# InputCurrentSensingSketch.net
KiCad netlist of a schematic drawn in Altium Designer
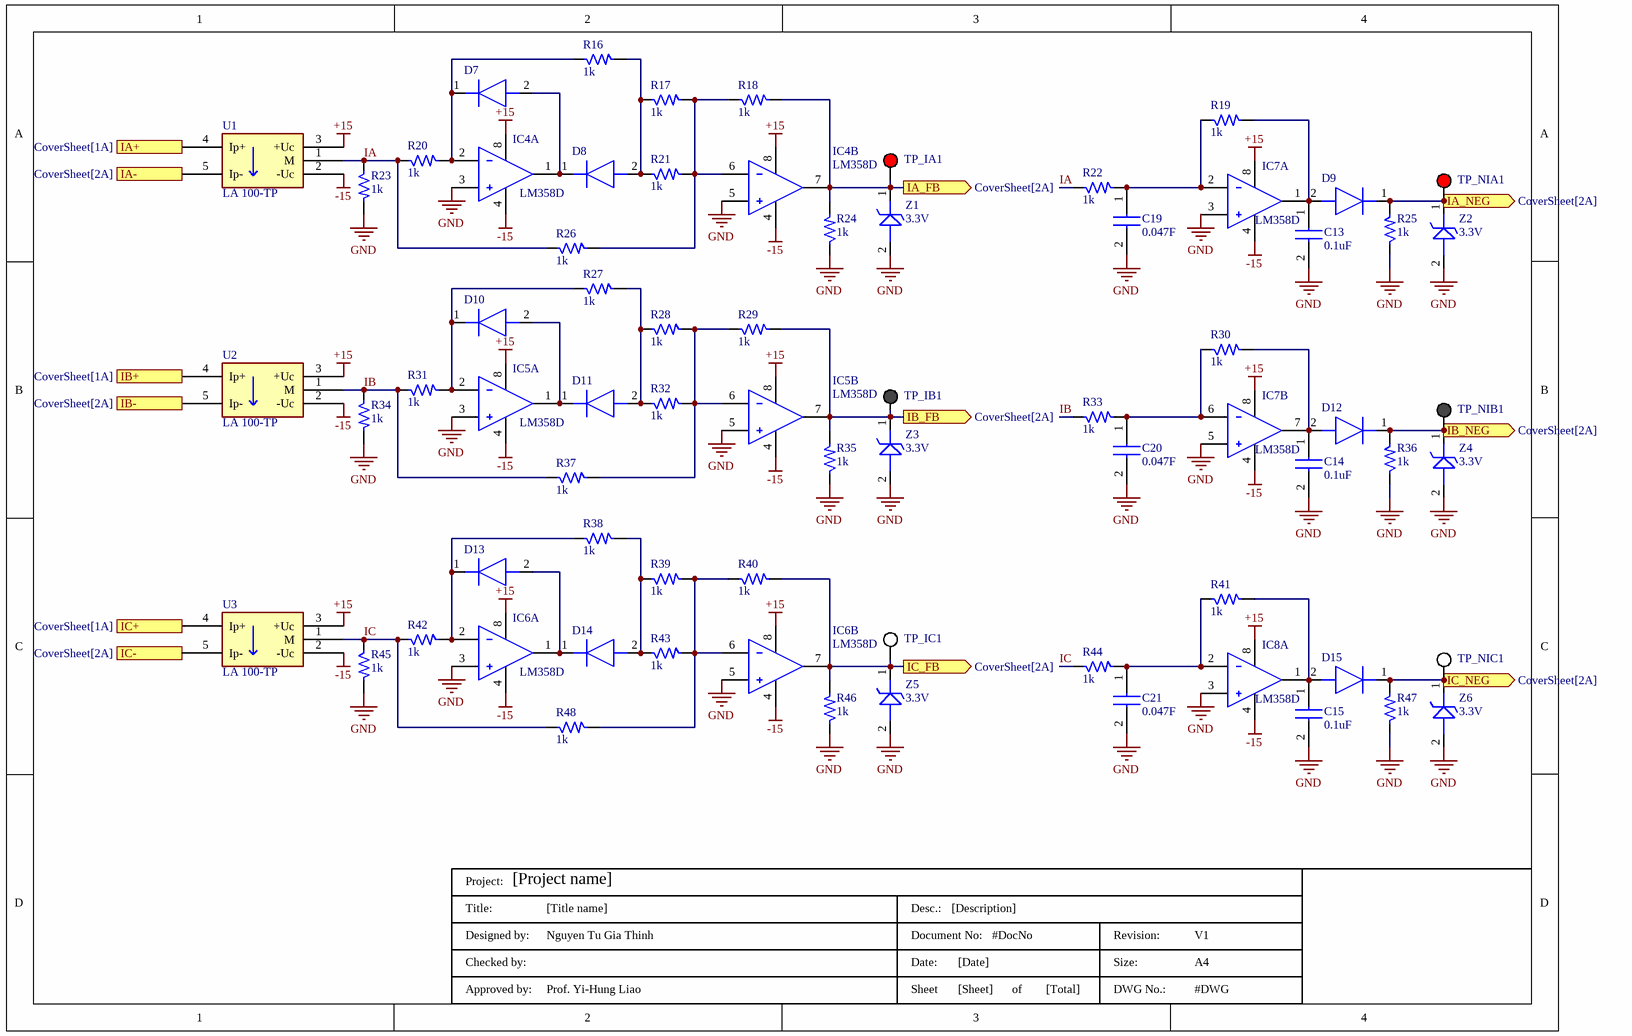
[diagram p0: InputCurrentSensingSketch.SchDoc]

(export (version "E")
  (design (tool "Eeschema 10.0.6"))
  (components
    (comp (ref "C13")
      (value "0.1uF")
      (footprint "SamacSys:C0805")
      (description "Capacitor")
      (fields
        (field (name "MANUFACTURER_PART_NUMBER") "C0805C104K3RACTU")
        (field (name "MOUSER PART NUMBER") "80-C0805C104K3R")
      )
      (libsource (lib "SamacSys") (part "C0805C104K3RACTU"))
    )
    (comp (ref "C14")
      (value "0.1uF")
      (footprint "SamacSys:C0805")
      (description "Capacitor")
      (fields
        (field (name "MANUFACTURER_PART_NUMBER") "C0805C104K3RACTU")
        (field (name "MOUSER PART NUMBER") "80-C0805C104K3R")
      )
      (libsource (lib "SamacSys") (part "C0805C104K3RACTU"))
    )
    (comp (ref "C15")
      (value "0.1uF")
      (footprint "SamacSys:C0805")
      (description "Capacitor")
      (fields
        (field (name "MANUFACTURER_PART_NUMBER") "C0805C104K3RACTU")
        (field (name "MOUSER PART NUMBER") "80-C0805C104K3R")
      )
      (libsource (lib "SamacSys") (part "C0805C104K3RACTU"))
    )
    (comp (ref "C19")
      (value "0.047F")
      (footprint "SamacSys:C0805")
      (description "Capacitor")
      (fields
        (field (name "MANUFACTURER_PART_NUMBER") "C0805C473F3GECAUTO7210")
        (field (name "MOUSER PART NUMBER") "80-C0805C473F3GEAULR")
      )
      (libsource (lib "*") (part "C0805C473F3GECAUTO7210"))
    )
    (comp (ref "C20")
      (value "0.047F")
      (footprint "SamacSys:C0805")
      (description "Capacitor")
      (fields
        (field (name "MANUFACTURER_PART_NUMBER") "C0805C473F3GECAUTO7210")
        (field (name "MOUSER PART NUMBER") "80-C0805C473F3GEAULR")
      )
      (libsource (lib "*") (part "C0805C473F3GECAUTO7210"))
    )
    (comp (ref "C21")
      (value "0.047F")
      (footprint "SamacSys:C0805")
      (description "Capacitor")
      (fields
        (field (name "MANUFACTURER_PART_NUMBER") "C0805C473F3GECAUTO7210")
        (field (name "MOUSER PART NUMBER") "80-C0805C473F3GEAULR")
      )
      (libsource (lib "*") (part "C0805C473F3GECAUTO7210"))
    )
    (comp (ref "D7")
      (value "MBRM130LT1G")
      (footprint "SamacSys:MBRM130LT1G")
      (description "Diode")
      (fields (field (name "MOUSER PART NUMBER") "863-MBRM130LT1G"))
      (libsource (lib "SamacSys") (part "MBRM130LT1G"))
    )
    (comp (ref "D8")
      (value "MBRM130LT1G")
      (footprint "SamacSys:MBRM130LT1G")
      (description "Diode")
      (fields (field (name "MOUSER PART NUMBER") "863-MBRM130LT1G"))
      (libsource (lib "SamacSys") (part "MBRM130LT1G"))
    )
    (comp (ref "D9")
      (value "MBRM130LT1G")
      (footprint "SamacSys:MBRM130LT1G")
      (description "Diode")
      (fields (field (name "MOUSER PART NUMBER") "863-MBRM130LT1G"))
      (libsource (lib "SamacSys") (part "MBRM130LT1G"))
    )
    (comp (ref "D10")
      (value "MBRM130LT1G")
      (footprint "SamacSys:MBRM130LT1G")
      (description "Diode")
      (fields (field (name "MOUSER PART NUMBER") "863-MBRM130LT1G"))
      (libsource (lib "SamacSys") (part "MBRM130LT1G"))
    )
    (comp (ref "D11")
      (value "MBRM130LT1G")
      (footprint "SamacSys:MBRM130LT1G")
      (description "Diode")
      (fields (field (name "MOUSER PART NUMBER") "863-MBRM130LT1G"))
      (libsource (lib "SamacSys") (part "MBRM130LT1G"))
    )
    (comp (ref "D12")
      (value "MBRM130LT1G")
      (footprint "SamacSys:MBRM130LT1G")
      (description "Diode")
      (fields (field (name "MOUSER PART NUMBER") "863-MBRM130LT1G"))
      (libsource (lib "SamacSys") (part "MBRM130LT1G"))
    )
    (comp (ref "D13")
      (value "MBRM130LT1G")
      (footprint "SamacSys:MBRM130LT1G")
      (description "Diode")
      (fields (field (name "MOUSER PART NUMBER") "863-MBRM130LT1G"))
      (libsource (lib "SamacSys") (part "MBRM130LT1G"))
    )
    (comp (ref "D14")
      (value "MBRM130LT1G")
      (footprint "SamacSys:MBRM130LT1G")
      (description "Diode")
      (fields (field (name "MOUSER PART NUMBER") "863-MBRM130LT1G"))
      (libsource (lib "SamacSys") (part "MBRM130LT1G"))
    )
    (comp (ref "D15")
      (value "MBRM130LT1G")
      (footprint "SamacSys:MBRM130LT1G")
      (description "Diode")
      (fields (field (name "MOUSER PART NUMBER") "863-MBRM130LT1G"))
      (libsource (lib "SamacSys") (part "MBRM130LT1G"))
    )
    (comp (ref "IC4")
      (value "LM358D")
      (footprint "SamacSys:SOIC127P600X175-8N")
      (description "Integrated Circuit")
      (fields (field (name "MOUSER PART NUMBER") "595-LM358D"))
      (libsource (lib "ViennaRectifier") (part "LM358D"))
    )
    (comp (ref "IC5")
      (value "LM358D")
      (footprint "SamacSys:SOIC127P600X175-8N")
      (description "Integrated Circuit")
      (fields (field (name "MOUSER PART NUMBER") "595-LM358D"))
      (libsource (lib "ViennaRectifier") (part "LM358D"))
    )
    (comp (ref "IC6")
      (value "LM358D")
      (footprint "SamacSys:SOIC127P600X175-8N")
      (description "Integrated Circuit")
      (fields (field (name "MOUSER PART NUMBER") "595-LM358D"))
      (libsource (lib "ViennaRectifier") (part "LM358D"))
    )
    (comp (ref "IC7")
      (value "LM358D")
      (footprint "SamacSys:SOIC127P600X175-8N")
      (description "Integrated Circuit")
      (fields (field (name "MOUSER PART NUMBER") "595-LM358D"))
      (libsource (lib "ViennaRectifier") (part "LM358D"))
    )
    (comp (ref "IC8")
      (value "LM358D")
      (footprint "SamacSys:SOIC127P600X175-8N")
      (description "Integrated Circuit")
      (fields (field (name "MOUSER PART NUMBER") "595-LM358D"))
      (libsource (lib "ViennaRectifier") (part "LM358D"))
    )
    (comp (ref "R16")
      (value "1k")
      (footprint "SM-1206")
      (description "Resistor 1/4W")
      (libsource (lib "ViennaRectifier") (part "R"))
    )
    (comp (ref "R17")
      (value "1k")
      (footprint "SM-1206")
      (description "Resistor 1/4W")
      (libsource (lib "ViennaRectifier") (part "R"))
    )
    (comp (ref "R18")
      (value "1k")
      (footprint "SM-1206")
      (description "Resistor 1/4W")
      (libsource (lib "ViennaRectifier") (part "R"))
    )
    (comp (ref "R19")
      (value "1k")
      (footprint "SM-1206")
      (description "Resistor 1/4W")
      (libsource (lib "ViennaRectifier") (part "R"))
    )
    (comp (ref "R20")
      (value "1k")
      (footprint "SM-1206")
      (description "Resistor 1/4W")
      (libsource (lib "ViennaRectifier") (part "R"))
    )
    (comp (ref "R21")
      (value "1k")
      (footprint "SM-1206")
      (description "Resistor 1/4W")
      (libsource (lib "ViennaRectifier") (part "R"))
    )
    (comp (ref "R22")
      (value "1k")
      (footprint "SM-1206")
      (description "Resistor 1/4W")
      (libsource (lib "ViennaRectifier") (part "R"))
    )
    (comp (ref "R23")
      (value "1k")
      (footprint "SM-1206")
      (description "Resistor 1/4W")
      (libsource (lib "ViennaRectifier") (part "R"))
    )
    (comp (ref "R24")
      (value "1k")
      (footprint "SM-1206")
      (description "Resistor 1/4W")
      (libsource (lib "ViennaRectifier") (part "R"))
    )
    (comp (ref "R25")
      (value "1k")
      (footprint "SM-1206")
      (description "Resistor 1/4W")
      (libsource (lib "ViennaRectifier") (part "R"))
    )
    (comp (ref "R26")
      (value "1k")
      (footprint "SM-1206")
      (description "Resistor 1/4W")
      (libsource (lib "ViennaRectifier") (part "R"))
    )
    (comp (ref "R27")
      (value "1k")
      (footprint "SM-1206")
      (description "Resistor 1/4W")
      (libsource (lib "ViennaRectifier") (part "R"))
    )
    (comp (ref "R28")
      (value "1k")
      (footprint "SM-1206")
      (description "Resistor 1/4W")
      (libsource (lib "ViennaRectifier") (part "R"))
    )
    (comp (ref "R29")
      (value "1k")
      (footprint "SM-1206")
      (description "Resistor 1/4W")
      (libsource (lib "ViennaRectifier") (part "R"))
    )
    (comp (ref "R30")
      (value "1k")
      (footprint "SM-1206")
      (description "Resistor 1/4W")
      (libsource (lib "ViennaRectifier") (part "R"))
    )
    (comp (ref "R31")
      (value "1k")
      (footprint "SM-1206")
      (description "Resistor 1/4W")
      (libsource (lib "ViennaRectifier") (part "R"))
    )
    (comp (ref "R32")
      (value "1k")
      (footprint "SM-1206")
      (description "Resistor 1/4W")
      (libsource (lib "ViennaRectifier") (part "R"))
    )
    (comp (ref "R33")
      (value "1k")
      (footprint "SM-1206")
      (description "Resistor 1/4W")
      (libsource (lib "ViennaRectifier") (part "R"))
    )
    (comp (ref "R34")
      (value "1k")
      (footprint "SM-1206")
      (description "Resistor 1/4W")
      (libsource (lib "ViennaRectifier") (part "R"))
    )
    (comp (ref "R35")
      (value "1k")
      (footprint "SM-1206")
      (description "Resistor 1/4W")
      (libsource (lib "ViennaRectifier") (part "R"))
    )
    (comp (ref "R36")
      (value "1k")
      (footprint "SM-1206")
      (description "Resistor 1/4W")
      (libsource (lib "ViennaRectifier") (part "R"))
    )
    (comp (ref "R37")
      (value "1k")
      (footprint "SM-1206")
      (description "Resistor 1/4W")
      (libsource (lib "ViennaRectifier") (part "R"))
    )
    (comp (ref "R38")
      (value "1k")
      (footprint "SM-1206")
      (description "Resistor 1/4W")
      (libsource (lib "ViennaRectifier") (part "R"))
    )
    (comp (ref "R39")
      (value "1k")
      (footprint "SM-1206")
      (description "Resistor 1/4W")
      (libsource (lib "ViennaRectifier") (part "R"))
    )
    (comp (ref "R40")
      (value "1k")
      (footprint "SM-1206")
      (description "Resistor 1/4W")
      (libsource (lib "ViennaRectifier") (part "R"))
    )
    (comp (ref "R41")
      (value "1k")
      (footprint "SM-1206")
      (description "Resistor 1/4W")
      (libsource (lib "ViennaRectifier") (part "R"))
    )
    (comp (ref "R42")
      (value "1k")
      (footprint "SM-1206")
      (description "Resistor 1/4W")
      (libsource (lib "ViennaRectifier") (part "R"))
    )
    (comp (ref "R43")
      (value "1k")
      (footprint "SM-1206")
      (description "Resistor 1/4W")
      (libsource (lib "ViennaRectifier") (part "R"))
    )
    (comp (ref "R44")
      (value "1k")
      (footprint "SM-1206")
      (description "Resistor 1/4W")
      (libsource (lib "ViennaRectifier") (part "R"))
    )
    (comp (ref "R45")
      (value "1k")
      (footprint "SM-1206")
      (description "Resistor 1/4W")
      (libsource (lib "ViennaRectifier") (part "R"))
    )
    (comp (ref "R46")
      (value "1k")
      (footprint "SM-1206")
      (description "Resistor 1/4W")
      (libsource (lib "ViennaRectifier") (part "R"))
    )
    (comp (ref "R47")
      (value "1k")
      (footprint "SM-1206")
      (description "Resistor 1/4W")
      (libsource (lib "ViennaRectifier") (part "R"))
    )
    (comp (ref "R48")
      (value "1k")
      (footprint "SM-1206")
      (description "Resistor 1/4W")
      (libsource (lib "ViennaRectifier") (part "R"))
    )
    (comp (ref "TP_IA1")
      (value "~")
      (footprint "5000")
      (description "Test Point Red, Multipurpose, TH")
      (libsource (lib "TestPointKeystone") (part "5000"))
    )
    (comp (ref "TP_IB1")
      (value "~")
      (footprint "5001")
      (description "Test Point Black, Multipurpose, TH")
      (libsource (lib "TestPointKeystone") (part "5001"))
    )
    (comp (ref "TP_IC1")
      (value "~")
      (footprint "5002")
      (description "Test Point White, Multipurpose, TH")
      (libsource (lib "TestPointKeystone") (part "5002"))
    )
    (comp (ref "TP_NIA1")
      (value "~")
      (footprint "5000")
      (description "Test Point Red, Multipurpose, TH")
      (libsource (lib "TestPointKeystone") (part "5000"))
    )
    (comp (ref "TP_NIB1")
      (value "~")
      (footprint "5001")
      (description "Test Point Black, Multipurpose, TH")
      (libsource (lib "TestPointKeystone") (part "5001"))
    )
    (comp (ref "TP_NIC1")
      (value "~")
      (footprint "5002")
      (description "Test Point White, Multipurpose, TH")
      (libsource (lib "TestPointKeystone") (part "5002"))
    )
    (comp (ref "U1")
      (value "LA 100-TP")
      (footprint "LA 100-TP")
      (description "Current Transducer, AC/AC, 100A")
      (libsource (lib "ViennaRectifier") (part "LA 100-TP"))
    )
    (comp (ref "U2")
      (value "LA 100-TP")
      (footprint "LA 100-TP")
      (description "Current Transducer, AC/AC, 100A")
      (libsource (lib "ViennaRectifier") (part "LA 100-TP"))
    )
    (comp (ref "U3")
      (value "LA 100-TP")
      (footprint "LA 100-TP")
      (description "Current Transducer, AC/AC, 100A")
      (libsource (lib "ViennaRectifier") (part "LA 100-TP"))
    )
    (comp (ref "Z1")
      (value "3.3V")
      (footprint "SamacSys:DIOM5226X230N")
      (description "Zener Diode")
      (fields
        (field (name "MANUFACTURER_PART_NUMBER") "BZG05C3V3-HM3-08")
        (field (name "MOUSER PART NUMBER") "78-BZG05C3V3-HM3-08")
      )
      (libsource (lib "SamacSys") (part "BZG05C3V3-HM3-08"))
    )
    (comp (ref "Z2")
      (value "3.3V")
      (footprint "SamacSys:DIOM5226X230N")
      (description "Zener Diode")
      (fields
        (field (name "MANUFACTURER_PART_NUMBER") "BZG05C3V3-HM3-08")
        (field (name "MOUSER PART NUMBER") "78-BZG05C3V3-HM3-08")
      )
      (libsource (lib "SamacSys") (part "BZG05C3V3-HM3-08"))
    )
    (comp (ref "Z3")
      (value "3.3V")
      (footprint "SamacSys:DIOM5226X230N")
      (description "Zener Diode")
      (fields
        (field (name "MANUFACTURER_PART_NUMBER") "BZG05C3V3-HM3-08")
        (field (name "MOUSER PART NUMBER") "78-BZG05C3V3-HM3-08")
      )
      (libsource (lib "SamacSys") (part "BZG05C3V3-HM3-08"))
    )
    (comp (ref "Z4")
      (value "3.3V")
      (footprint "SamacSys:DIOM5226X230N")
      (description "Zener Diode")
      (fields
        (field (name "MANUFACTURER_PART_NUMBER") "BZG05C3V3-HM3-08")
        (field (name "MOUSER PART NUMBER") "78-BZG05C3V3-HM3-08")
      )
      (libsource (lib "SamacSys") (part "BZG05C3V3-HM3-08"))
    )
    (comp (ref "Z5")
      (value "3.3V")
      (footprint "SamacSys:DIOM5226X230N")
      (description "Zener Diode")
      (fields
        (field (name "MANUFACTURER_PART_NUMBER") "BZG05C3V3-HM3-08")
        (field (name "MOUSER PART NUMBER") "78-BZG05C3V3-HM3-08")
      )
      (libsource (lib "SamacSys") (part "BZG05C3V3-HM3-08"))
    )
    (comp (ref "Z6")
      (value "3.3V")
      (footprint "SamacSys:DIOM5226X230N")
      (description "Zener Diode")
      (fields
        (field (name "MANUFACTURER_PART_NUMBER") "BZG05C3V3-HM3-08")
        (field (name "MOUSER PART NUMBER") "78-BZG05C3V3-HM3-08")
      )
      (libsource (lib "SamacSys") (part "BZG05C3V3-HM3-08"))
    )
  )
  (nets
    (net (code "1") (name "+15") (class "Default")
      (node (ref "IC4") (pin "8") (pinfunction "V+_8") (pintype "passive"))
      (node (ref "IC5") (pin "8") (pinfunction "V+_8") (pintype "passive"))
      (node (ref "IC6") (pin "8") (pinfunction "V+_8") (pintype "passive"))
      (node (ref "IC7") (pin "8") (pinfunction "V+_8") (pintype "passive"))
      (node (ref "IC8") (pin "8") (pinfunction "V+_8") (pintype "passive"))
      (node (ref "U1") (pin "3") (pinfunction "+Uc_3") (pintype "passive"))
      (node (ref "U2") (pin "3") (pinfunction "+Uc_3") (pintype "passive"))
      (node (ref "U3") (pin "3") (pinfunction "+Uc_3") (pintype "passive"))
    )
    (net (code "2") (name "-15") (class "Default")
      (node (ref "IC4") (pin "4") (pinfunction "V-_4") (pintype "passive"))
      (node (ref "IC5") (pin "4") (pinfunction "V-_4") (pintype "passive"))
      (node (ref "IC6") (pin "4") (pinfunction "V-_4") (pintype "passive"))
      (node (ref "IC7") (pin "4") (pinfunction "V-_4") (pintype "passive"))
      (node (ref "IC8") (pin "4") (pinfunction "V-_4") (pintype "passive"))
      (node (ref "U1") (pin "2") (pinfunction "-Uc_2") (pintype "passive"))
      (node (ref "U2") (pin "2") (pinfunction "-Uc_2") (pintype "passive"))
      (node (ref "U3") (pin "2") (pinfunction "-Uc_2") (pintype "passive"))
    )
    (net (code "3") (name "/IA") (class "Default")
      (node (ref "R20") (pin "1") (pinfunction "1_1") (pintype "passive"))
      (node (ref "R22") (pin "1") (pinfunction "1_1") (pintype "passive"))
      (node (ref "R23") (pin "1") (pinfunction "1_1") (pintype "passive"))
      (node (ref "R26") (pin "1") (pinfunction "1_1") (pintype "passive"))
      (node (ref "U1") (pin "1") (pinfunction "M_1") (pintype "passive"))
    )
    (net (code "4") (name "/IA+") (class "Default")
      (node (ref "U1") (pin "4") (pinfunction "Ip+_4") (pintype "passive"))
    )
    (net (code "5") (name "/IA-") (class "Default")
      (node (ref "U1") (pin "5") (pinfunction "Ip-_5") (pintype "passive"))
    )
    (net (code "6") (name "/IA_FB") (class "Default")
      (node (ref "IC4") (pin "7") (pinfunction "OUT2_7") (pintype "passive"))
      (node (ref "R18") (pin "2") (pinfunction "2_2") (pintype "passive"))
      (node (ref "R24") (pin "2") (pinfunction "2_2") (pintype "passive"))
      (node (ref "TP_IA1") (pin "1") (pinfunction "1_1") (pintype "passive"))
      (node (ref "Z1") (pin "1") (pinfunction "K_1") (pintype "passive"))
    )
    (net (code "7") (name "/IA_NEG") (class "Default")
      (node (ref "D9") (pin "1") (pinfunction "K_1") (pintype "passive"))
      (node (ref "R25") (pin "2") (pinfunction "2_2") (pintype "passive"))
      (node (ref "TP_NIA1") (pin "1") (pinfunction "1_1") (pintype "passive"))
      (node (ref "Z2") (pin "1") (pinfunction "K_1") (pintype "passive"))
    )
    (net (code "8") (name "/IB") (class "Default")
      (node (ref "R31") (pin "1") (pinfunction "1_1") (pintype "passive"))
      (node (ref "R33") (pin "1") (pinfunction "1_1") (pintype "passive"))
      (node (ref "R34") (pin "1") (pinfunction "1_1") (pintype "passive"))
      (node (ref "R37") (pin "1") (pinfunction "1_1") (pintype "passive"))
      (node (ref "U2") (pin "1") (pinfunction "M_1") (pintype "passive"))
    )
    (net (code "9") (name "/IB+") (class "Default")
      (node (ref "U2") (pin "4") (pinfunction "Ip+_4") (pintype "passive"))
    )
    (net (code "10") (name "/IB-") (class "Default")
      (node (ref "U2") (pin "5") (pinfunction "Ip-_5") (pintype "passive"))
    )
    (net (code "11") (name "/IB_FB") (class "Default")
      (node (ref "IC5") (pin "7") (pinfunction "OUT2_7") (pintype "passive"))
      (node (ref "R29") (pin "2") (pinfunction "2_2") (pintype "passive"))
      (node (ref "R35") (pin "2") (pinfunction "2_2") (pintype "passive"))
      (node (ref "TP_IB1") (pin "1") (pinfunction "1_1") (pintype "passive"))
      (node (ref "Z3") (pin "1") (pinfunction "K_1") (pintype "passive"))
    )
    (net (code "12") (name "/IB_NEG") (class "Default")
      (node (ref "D12") (pin "1") (pinfunction "K_1") (pintype "passive"))
      (node (ref "R36") (pin "2") (pinfunction "2_2") (pintype "passive"))
      (node (ref "TP_NIB1") (pin "1") (pinfunction "1_1") (pintype "passive"))
      (node (ref "Z4") (pin "1") (pinfunction "K_1") (pintype "passive"))
    )
    (net (code "13") (name "/IC") (class "Default")
      (node (ref "R42") (pin "1") (pinfunction "1_1") (pintype "passive"))
      (node (ref "R44") (pin "1") (pinfunction "1_1") (pintype "passive"))
      (node (ref "R45") (pin "1") (pinfunction "1_1") (pintype "passive"))
      (node (ref "R48") (pin "1") (pinfunction "1_1") (pintype "passive"))
      (node (ref "U3") (pin "1") (pinfunction "M_1") (pintype "passive"))
    )
    (net (code "14") (name "/IC+") (class "Default")
      (node (ref "U3") (pin "4") (pinfunction "Ip+_4") (pintype "passive"))
    )
    (net (code "15") (name "/IC-") (class "Default")
      (node (ref "U3") (pin "5") (pinfunction "Ip-_5") (pintype "passive"))
    )
    (net (code "16") (name "/IC_FB") (class "Default")
      (node (ref "IC6") (pin "7") (pinfunction "OUT2_7") (pintype "passive"))
      (node (ref "R40") (pin "2") (pinfunction "2_2") (pintype "passive"))
      (node (ref "R46") (pin "2") (pinfunction "2_2") (pintype "passive"))
      (node (ref "TP_IC1") (pin "1") (pinfunction "1_1") (pintype "passive"))
      (node (ref "Z5") (pin "1") (pinfunction "K_1") (pintype "passive"))
    )
    (net (code "17") (name "/IC_NEG") (class "Default")
      (node (ref "D15") (pin "1") (pinfunction "K_1") (pintype "passive"))
      (node (ref "R47") (pin "2") (pinfunction "2_2") (pintype "passive"))
      (node (ref "TP_NIC1") (pin "1") (pinfunction "1_1") (pintype "passive"))
      (node (ref "Z6") (pin "1") (pinfunction "K_1") (pintype "passive"))
    )
    (net (code "18") (name "GND") (class "Default")
      (node (ref "C13") (pin "2") (pinfunction "2_2") (pintype "passive"))
      (node (ref "C14") (pin "2") (pinfunction "2_2") (pintype "passive"))
      (node (ref "C15") (pin "2") (pinfunction "2_2") (pintype "passive"))
      (node (ref "C19") (pin "2") (pinfunction "2_2") (pintype "passive"))
      (node (ref "C20") (pin "2") (pinfunction "2_2") (pintype "passive"))
      (node (ref "C21") (pin "2") (pinfunction "2_2") (pintype "passive"))
      (node (ref "IC4") (pin "3") (pinfunction "IN1+_3") (pintype "passive"))
      (node (ref "IC4") (pin "5") (pinfunction "IN2+_5") (pintype "passive"))
      (node (ref "IC5") (pin "3") (pinfunction "IN1+_3") (pintype "passive"))
      (node (ref "IC5") (pin "5") (pinfunction "IN2+_5") (pintype "passive"))
      (node (ref "IC6") (pin "3") (pinfunction "IN1+_3") (pintype "passive"))
      (node (ref "IC6") (pin "5") (pinfunction "IN2+_5") (pintype "passive"))
      (node (ref "IC7") (pin "3") (pinfunction "IN1+_3") (pintype "passive"))
      (node (ref "IC7") (pin "5") (pinfunction "IN2+_5") (pintype "passive"))
      (node (ref "IC8") (pin "3") (pinfunction "IN1+_3") (pintype "passive"))
      (node (ref "R23") (pin "2") (pinfunction "2_2") (pintype "passive"))
      (node (ref "R24") (pin "1") (pinfunction "1_1") (pintype "passive"))
      (node (ref "R25") (pin "1") (pinfunction "1_1") (pintype "passive"))
      (node (ref "R34") (pin "2") (pinfunction "2_2") (pintype "passive"))
      (node (ref "R35") (pin "1") (pinfunction "1_1") (pintype "passive"))
      (node (ref "R36") (pin "1") (pinfunction "1_1") (pintype "passive"))
      (node (ref "R45") (pin "2") (pinfunction "2_2") (pintype "passive"))
      (node (ref "R46") (pin "1") (pinfunction "1_1") (pintype "passive"))
      (node (ref "R47") (pin "1") (pinfunction "1_1") (pintype "passive"))
      (node (ref "Z1") (pin "2") (pinfunction "A_2") (pintype "passive"))
      (node (ref "Z2") (pin "2") (pinfunction "A_2") (pintype "passive"))
      (node (ref "Z3") (pin "2") (pinfunction "A_2") (pintype "passive"))
      (node (ref "Z4") (pin "2") (pinfunction "A_2") (pintype "passive"))
      (node (ref "Z5") (pin "2") (pinfunction "A_2") (pintype "passive"))
      (node (ref "Z6") (pin "2") (pinfunction "A_2") (pintype "passive"))
    )
    (net (code "19") (name "Net-(D7-A)") (class "Default")
      (node (ref "D7") (pin "2") (pinfunction "A_2") (pintype "passive"))
      (node (ref "D8") (pin "1") (pinfunction "K_1") (pintype "passive"))
      (node (ref "IC4") (pin "1") (pinfunction "OUT1_1") (pintype "passive"))
    )
    (net (code "20") (name "Net-(D7-K)") (class "Default")
      (node (ref "D7") (pin "1") (pinfunction "K_1") (pintype "passive"))
      (node (ref "IC4") (pin "2") (pinfunction "IN1-_2") (pintype "passive"))
      (node (ref "R16") (pin "1") (pinfunction "1_1") (pintype "passive"))
      (node (ref "R20") (pin "2") (pinfunction "2_2") (pintype "passive"))
    )
    (net (code "21") (name "Net-(D8-A)") (class "Default")
      (node (ref "D8") (pin "2") (pinfunction "A_2") (pintype "passive"))
      (node (ref "R16") (pin "2") (pinfunction "2_2") (pintype "passive"))
      (node (ref "R17") (pin "1") (pinfunction "1_1") (pintype "passive"))
      (node (ref "R21") (pin "1") (pinfunction "1_1") (pintype "passive"))
    )
    (net (code "22") (name "Net-(D9-A)") (class "Default")
      (node (ref "C13") (pin "1") (pinfunction "1_1") (pintype "passive"))
      (node (ref "D9") (pin "2") (pinfunction "A_2") (pintype "passive"))
      (node (ref "IC7") (pin "1") (pinfunction "OUT1_1") (pintype "passive"))
      (node (ref "R19") (pin "2") (pinfunction "2_2") (pintype "passive"))
    )
    (net (code "23") (name "Net-(D10-A)") (class "Default")
      (node (ref "D10") (pin "2") (pinfunction "A_2") (pintype "passive"))
      (node (ref "D11") (pin "1") (pinfunction "K_1") (pintype "passive"))
      (node (ref "IC5") (pin "1") (pinfunction "OUT1_1") (pintype "passive"))
    )
    (net (code "24") (name "Net-(D10-K)") (class "Default")
      (node (ref "D10") (pin "1") (pinfunction "K_1") (pintype "passive"))
      (node (ref "IC5") (pin "2") (pinfunction "IN1-_2") (pintype "passive"))
      (node (ref "R27") (pin "1") (pinfunction "1_1") (pintype "passive"))
      (node (ref "R31") (pin "2") (pinfunction "2_2") (pintype "passive"))
    )
    (net (code "25") (name "Net-(D11-A)") (class "Default")
      (node (ref "D11") (pin "2") (pinfunction "A_2") (pintype "passive"))
      (node (ref "R27") (pin "2") (pinfunction "2_2") (pintype "passive"))
      (node (ref "R28") (pin "1") (pinfunction "1_1") (pintype "passive"))
      (node (ref "R32") (pin "1") (pinfunction "1_1") (pintype "passive"))
    )
    (net (code "26") (name "Net-(D12-A)") (class "Default")
      (node (ref "C14") (pin "1") (pinfunction "1_1") (pintype "passive"))
      (node (ref "D12") (pin "2") (pinfunction "A_2") (pintype "passive"))
      (node (ref "IC7") (pin "7") (pinfunction "OUT2_7") (pintype "passive"))
      (node (ref "R30") (pin "2") (pinfunction "2_2") (pintype "passive"))
    )
    (net (code "27") (name "Net-(D13-A)") (class "Default")
      (node (ref "D13") (pin "2") (pinfunction "A_2") (pintype "passive"))
      (node (ref "D14") (pin "1") (pinfunction "K_1") (pintype "passive"))
      (node (ref "IC6") (pin "1") (pinfunction "OUT1_1") (pintype "passive"))
    )
    (net (code "28") (name "Net-(D13-K)") (class "Default")
      (node (ref "D13") (pin "1") (pinfunction "K_1") (pintype "passive"))
      (node (ref "IC6") (pin "2") (pinfunction "IN1-_2") (pintype "passive"))
      (node (ref "R38") (pin "1") (pinfunction "1_1") (pintype "passive"))
      (node (ref "R42") (pin "2") (pinfunction "2_2") (pintype "passive"))
    )
    (net (code "29") (name "Net-(D14-A)") (class "Default")
      (node (ref "D14") (pin "2") (pinfunction "A_2") (pintype "passive"))
      (node (ref "R38") (pin "2") (pinfunction "2_2") (pintype "passive"))
      (node (ref "R39") (pin "1") (pinfunction "1_1") (pintype "passive"))
      (node (ref "R43") (pin "1") (pinfunction "1_1") (pintype "passive"))
    )
    (net (code "30") (name "Net-(D15-A)") (class "Default")
      (node (ref "C15") (pin "1") (pinfunction "1_1") (pintype "passive"))
      (node (ref "D15") (pin "2") (pinfunction "A_2") (pintype "passive"))
      (node (ref "IC8") (pin "1") (pinfunction "OUT1_1") (pintype "passive"))
      (node (ref "R41") (pin "2") (pinfunction "2_2") (pintype "passive"))
    )
    (net (code "31") (name "Net-(IC4B-IN2-)") (class "Default")
      (node (ref "IC4") (pin "6") (pinfunction "IN2-_6") (pintype "passive"))
      (node (ref "R17") (pin "2") (pinfunction "2_2") (pintype "passive"))
      (node (ref "R18") (pin "1") (pinfunction "1_1") (pintype "passive"))
      (node (ref "R21") (pin "2") (pinfunction "2_2") (pintype "passive"))
      (node (ref "R26") (pin "2") (pinfunction "2_2") (pintype "passive"))
    )
    (net (code "32") (name "Net-(IC5B-IN2-)") (class "Default")
      (node (ref "IC5") (pin "6") (pinfunction "IN2-_6") (pintype "passive"))
      (node (ref "R28") (pin "2") (pinfunction "2_2") (pintype "passive"))
      (node (ref "R29") (pin "1") (pinfunction "1_1") (pintype "passive"))
      (node (ref "R32") (pin "2") (pinfunction "2_2") (pintype "passive"))
      (node (ref "R37") (pin "2") (pinfunction "2_2") (pintype "passive"))
    )
    (net (code "33") (name "Net-(IC6B-IN2-)") (class "Default")
      (node (ref "IC6") (pin "6") (pinfunction "IN2-_6") (pintype "passive"))
      (node (ref "R39") (pin "2") (pinfunction "2_2") (pintype "passive"))
      (node (ref "R40") (pin "1") (pinfunction "1_1") (pintype "passive"))
      (node (ref "R43") (pin "2") (pinfunction "2_2") (pintype "passive"))
      (node (ref "R48") (pin "2") (pinfunction "2_2") (pintype "passive"))
    )
    (net (code "34") (name "Net-(IC7A-IN1-)") (class "Default")
      (node (ref "C19") (pin "1") (pinfunction "1_1") (pintype "passive"))
      (node (ref "IC7") (pin "2") (pinfunction "IN1-_2") (pintype "passive"))
      (node (ref "R19") (pin "1") (pinfunction "1_1") (pintype "passive"))
      (node (ref "R22") (pin "2") (pinfunction "2_2") (pintype "passive"))
    )
    (net (code "35") (name "Net-(IC7B-IN2-)") (class "Default")
      (node (ref "C20") (pin "1") (pinfunction "1_1") (pintype "passive"))
      (node (ref "IC7") (pin "6") (pinfunction "IN2-_6") (pintype "passive"))
      (node (ref "R30") (pin "1") (pinfunction "1_1") (pintype "passive"))
      (node (ref "R33") (pin "2") (pinfunction "2_2") (pintype "passive"))
    )
    (net (code "36") (name "Net-(IC8A-IN1-)") (class "Default")
      (node (ref "C21") (pin "1") (pinfunction "1_1") (pintype "passive"))
      (node (ref "IC8") (pin "2") (pinfunction "IN1-_2") (pintype "passive"))
      (node (ref "R41") (pin "1") (pinfunction "1_1") (pintype "passive"))
      (node (ref "R44") (pin "2") (pinfunction "2_2") (pintype "passive"))
    )
  )
)
